# SimGEKI2_FrontIO.net
KiCad netlist of a schematic drawn in EasyEDA Pro
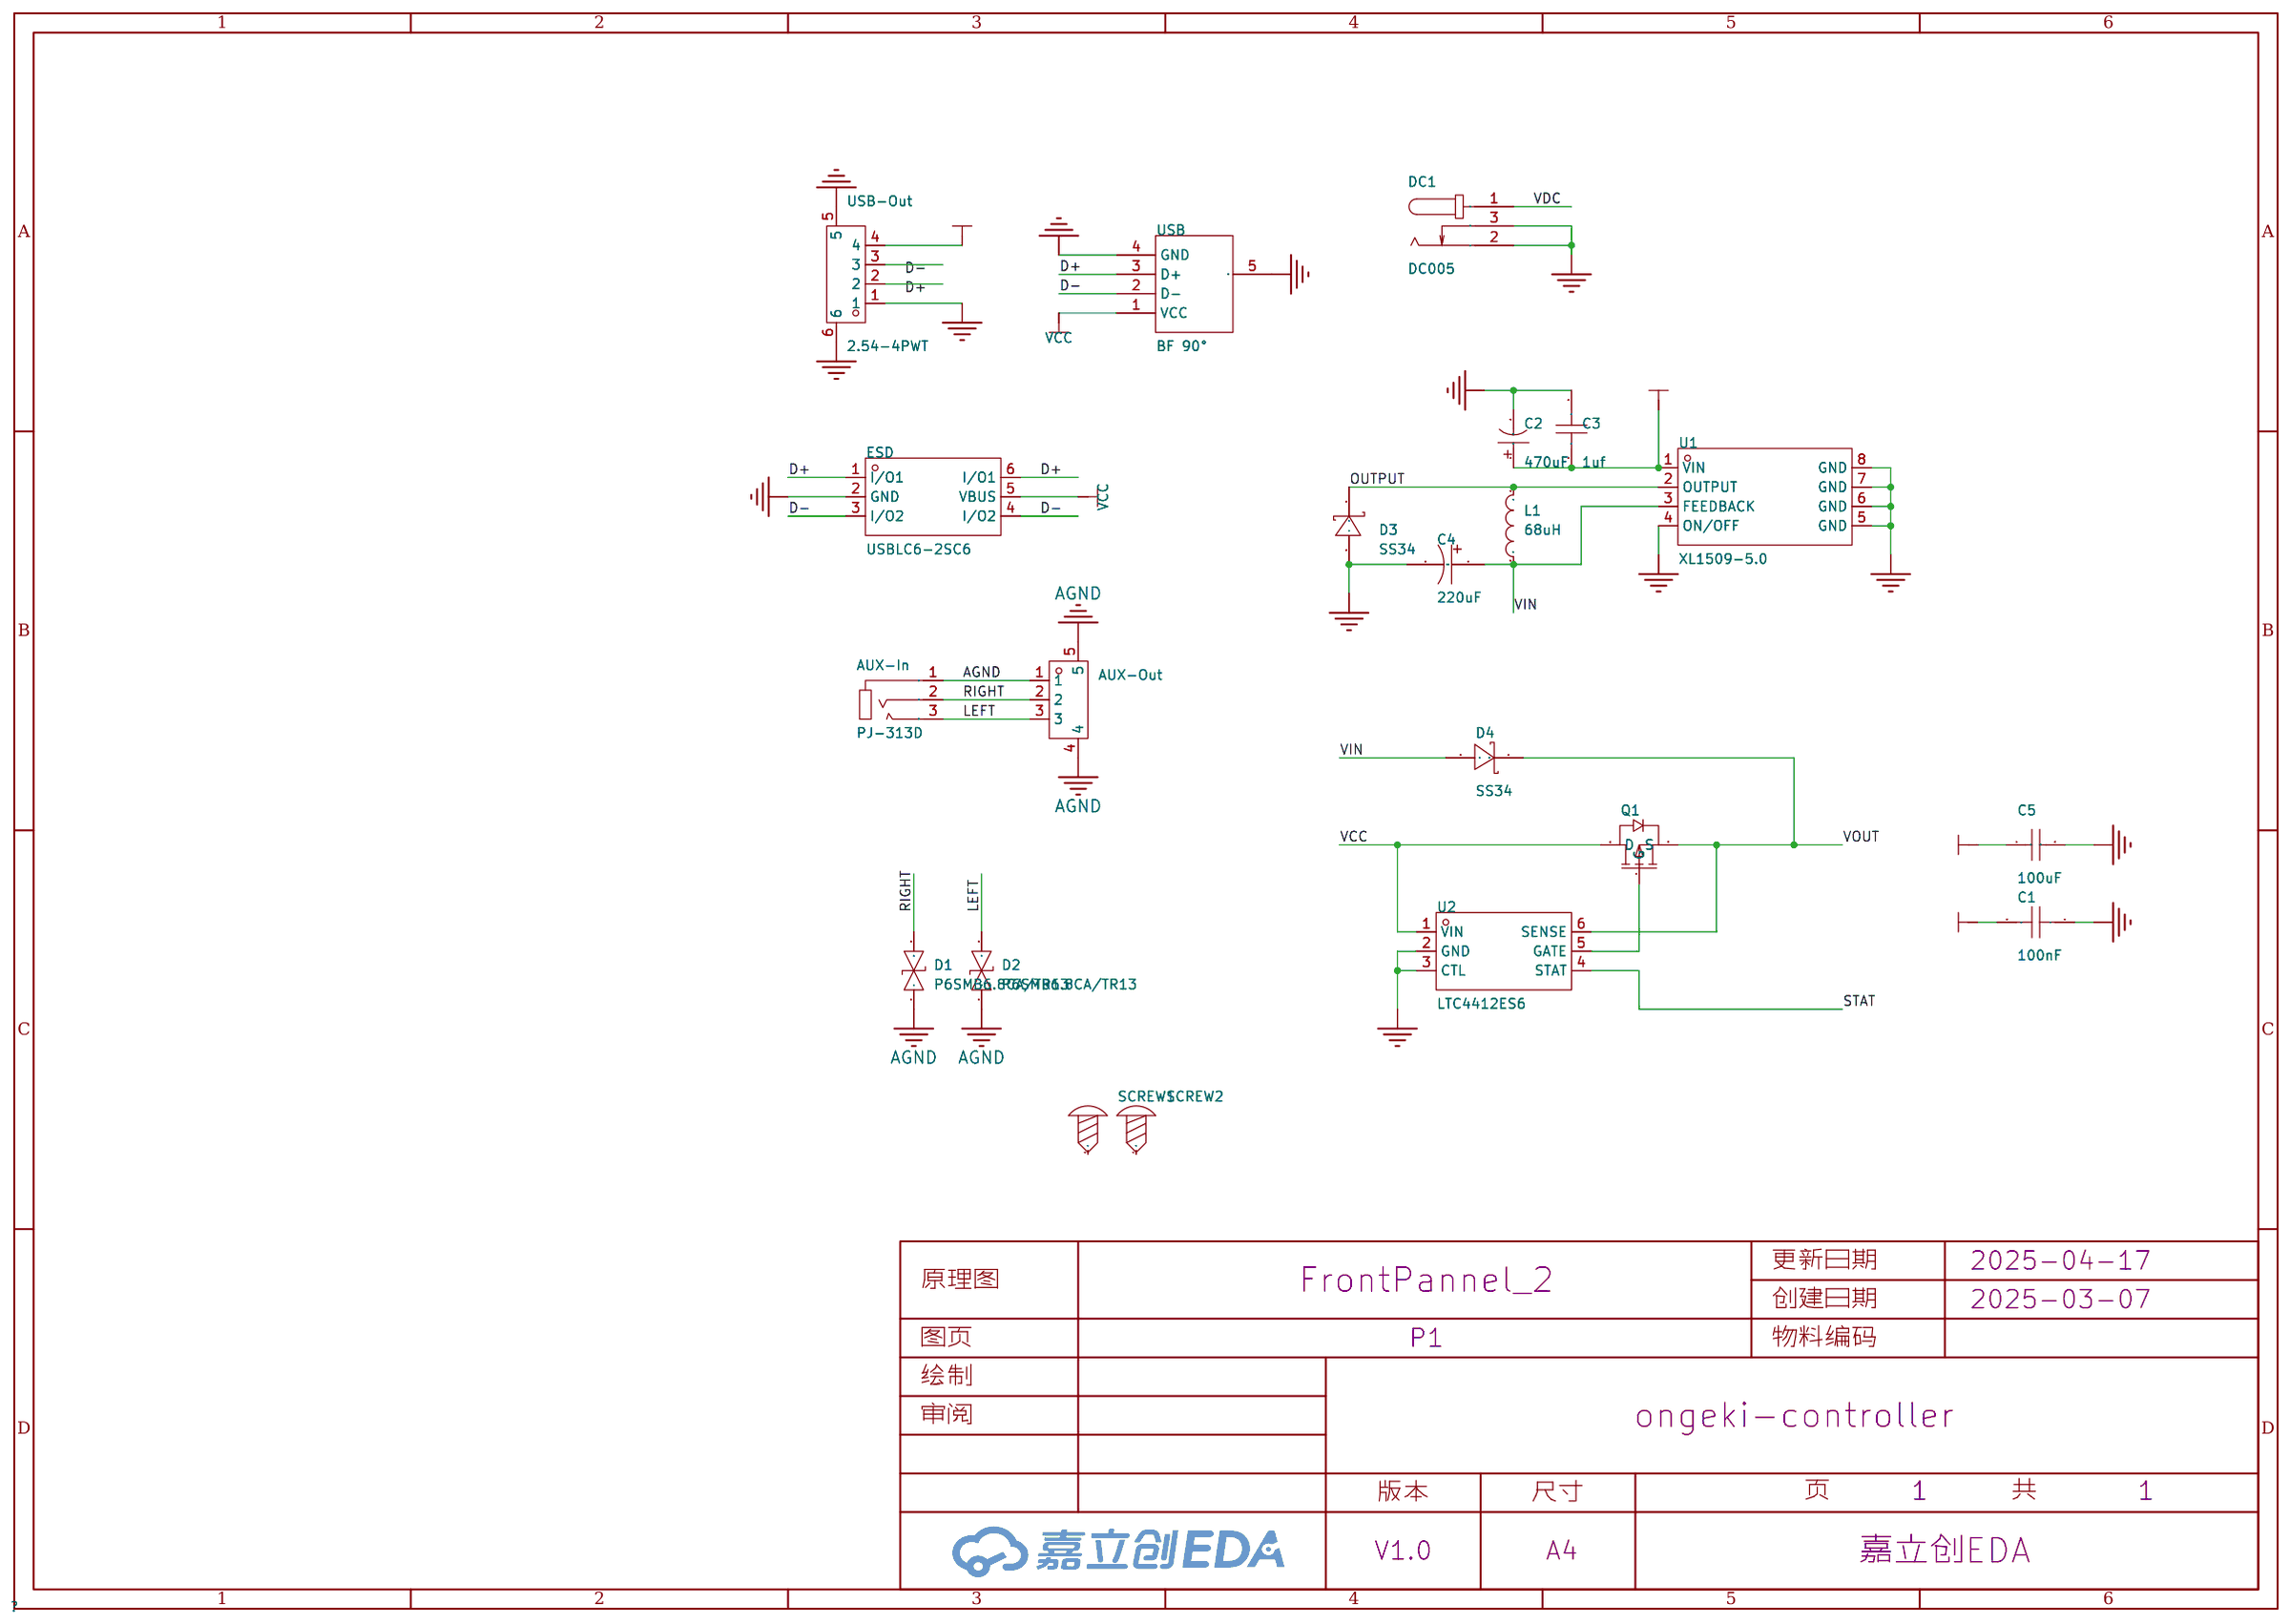
[diagram p0: schematic sheet]

(export (version "E")
  (design (tool "Eeschema 10.0.6"))
  (components
    (comp (ref "AUX-In")
      (value "PJ-313D")
      (footprint "easyedapro:AUDIO-SMD_PJ-313D-2")
      (description "连接器类型:3.5mm耳机座;额定电流:500mA;额定电压:30V;工作温度范围:-30°C~+70°C;")
      (fields (field (name "Manufacturer") "SHOU HAN(首韩)"))
      (libsource (lib "easyedapro") (part "PJ-313D_C668608"))
    )
    (comp (ref "AUX-Out")
      (value "WAFER-PH2.0-3PWB")
      (footprint "easyedapro:CONN-SMD_3P-P2.00_XUNPU_WAFER-PH2.0-3PWB")
      (description "插针结构:1x3P;间距:2mm;安装方式:卧贴;总PIN数:3P;排数:1;每排PIN数:3;额定电流:2A;工作温度范围:-25°C~+85°C;")
      (fields (field (name "Manufacturer") "XUNPU(讯普)"))
      (libsource (lib "easyedapro") (part "WAFER-PH2.0-3PWB"))
    )
    (comp (ref "C1")
      (value "100nF")
      (footprint "easyedapro:C0603")
      (libsource (lib "easyedapro") (part "CapAcitance"))
    )
    (comp (ref "C2")
      (value "470uF")
      (footprint "easyedapro:CAP-SMD_BD10.0-L10.3-W10.3-LS11.0-R-RD")
      (description "容值:470uF;精度:±20%;额定电压:35V;纹波电流:286mA@120Hz;等效串联电阻(ESR):-;")
      (fields (field (name "Manufacturer Part") "RVT1V471M1010") (field (name "Manufacturer") "ROQANG(容强)"))
      (libsource (lib "easyedapro") (part "RVT1V471M1010-C72519"))
    )
    (comp (ref "C3")
      (value "1uf")
      (footprint "easyedapro:C0603")
      (libsource (lib "easyedapro") (part "CapAcitance"))
    )
    (comp (ref "C4")
      (value "220uF")
      (fields (field (name "Manufacturer Part") "RVT1C221M0607") (field (name "Manufacturer") "ROQANG(容强)"))
      (libsource (lib "easyedapro") (part "VT1V221M0810"))
    )
    (comp (ref "C5")
      (value "100uF")
      (footprint "easyedapro:C1206")
      (description "容值:100uF;精度:±20%;额定电压:6.3V;材质(温度系数):X5R;")
      (fields
        (field (name "Manufacturer Part") "CL31A107MQHNNNE")
        (field (name "Manufacturer") "SAMSUNG(三星)")
      )
      (libsource (lib "easyedapro") (part "CL31A107MQHNNNE"))
    )
    (comp (ref "D1")
      (value "P6SMB6.8CA/TR13")
      (footprint "easyedapro:SMB_L4.6-W3.6-LS5.3-BI")
      (description "反向截止电压(Vrwm):5.8V;钳位电压:10.5V;峰值脉冲电流(Ipp):58.1A;峰值脉冲功率(Ppp):600W;击穿电压:6.45V;")
      (fields (field (name "Manufacturer") "Brightking(君耀电子)"))
      (libsource (lib "easyedapro") (part "P6SMB6.8CA-C78395"))
    )
    (comp (ref "D2")
      (value "P6SMB6.8CA/TR13")
      (footprint "easyedapro:SMB_L4.6-W3.6-LS5.3-BI")
      (description "反向截止电压(Vrwm):5.8V;钳位电压:10.5V;峰值脉冲电流(Ipp):58.1A;峰值脉冲功率(Ppp):600W;击穿电压:6.45V;")
      (fields (field (name "Manufacturer") "Brightking(君耀电子)"))
      (libsource (lib "easyedapro") (part "P6SMB6.8CA-C78395"))
    )
    (comp (ref "D3")
      (value "SS34")
      (footprint "easyedapro:SMA_L4.3-W2.6-LS5.2-RD")
      (description "二极管配置:独立式;正向压降(Vf):550mV@3A;直流反向耐压(Vr):40V;整流电流:3A;")
      (fields (field (name "Manufacturer") "MDD(辰达半导体)"))
      (libsource (lib "easyedapro") (part "SS34_C8678"))
    )
    (comp (ref "D4")
      (value "SS34")
      (footprint "easyedapro:SMA_L4.3-W2.6-LS5.2-RD")
      (description "二极管配置:独立式;正向压降(Vf):550mV@3A;直流反向耐压(Vr):40V;整流电流:3A;")
      (fields (field (name "Manufacturer") "MDD(辰达半导体)"))
      (libsource (lib "easyedapro") (part "SS34_C8678"))
    )
    (comp (ref "DC1")
      (value "DC005")
      (footprint "easyedapro:DC-IN-TH_DC005")
      (description "连接器类型:DC电源插座;安装方式:弯插;触点内径:2mm;触点外径:6.3mm;额定电流:500mA;额定电压:30V;工作温度范围:-25°C~+70°C;")
      (fields (field (name "Manufacturer") "SHOU HAN(首韩)"))
      (libsource (lib "easyedapro") (part "DC005_C431533"))
    )
    (comp (ref "ESD")
      (value "USBLC6-2SC6")
      (footprint "easyedapro:SOT-23-6_L2.9-W1.6-P0.95-LS2.8-BL")
      (fields (field (name "Manufacturer") "UMW(广东友台半导体)"))
      (libsource (lib "easyedapro") (part "USBLC6-2SC6_C2687116"))
    )
    (comp (ref "L1")
      (value "68uH")
      (footprint "easyedapro:IND-SMD_L7.1-W6.6")
      (description "电感值:68uH;精度:±20%;额定电流:1.5A;饱和电流(Isat):2A;类型:一体成型电感;")
      (fields (field (name "Manufacturer Part") "SMMS0650-680M") (field (name "Manufacturer") "SXN(顺翔诺)"))
      (libsource (lib "easyedapro") (part "SMMS0650-680M"))
    )
    (comp (ref "Q1")
      (value "~")
      (footprint "easyedapro:AO3401A_SOT-23-3")
      (libsource (lib "easyedapro") (part "P_MOS"))
    )
    (comp (ref "SCREW1")
      (value "~")
      (footprint "easyedapro:M4螺丝")
      (libsource (lib "easyedapro") (part "螺丝孔"))
    )
    (comp (ref "SCREW2")
      (value "~")
      (footprint "easyedapro:M4螺丝")
      (libsource (lib "easyedapro") (part "螺丝孔"))
    )
    (comp (ref "U1")
      (value "XL1509-5.0")
      (footprint "easyedapro:SOIC-8_L4.9-W3.9-P1.27-LS6.0-TR")
      (description "功能类型:降压型;输出类型:固定;工作电压:4.5V~40V;输出电压:5V;输出电流:2A;")
      (fields (field (name "Manufacturer") "UMW(友台半导体)"))
      (libsource (lib "easyedapro") (part "XL1509-5.0_C2902368"))
    )
    (comp (ref "U2")
      (value "LTC4412ES6")
      (footprint "easyedapro:TSOT-23-6_L2.9-W1.6-P0.95-LS2.8-BR")
      (description "电源电压:2.5V~28V;")
      (fields (field (name "Manufacturer") "ADI(亚德诺)"))
      (libsource (lib "easyedapro") (part "LTC4412ES6#TRPBF"))
    )
    (comp (ref "USB")
      (value "BF 90°")
      (footprint "easyedapro:USB-B_TH_BF90")
      (description "连接器类型:Type-B;标准:USB 2.0;公母:母;端口数量:1;触点数量:4P;安装方式:弯插;额定电流 - 电源:1.5A;工作温度范围:-25°C~+85°C;")
      (fields (field (name "Manufacturer") "SHOU HAN(首韩)"))
      (libsource (lib "easyedapro") (part "BF 90°"))
    )
    (comp (ref "USB-Out")
      (value "2.54-4PWT")
      (footprint "easyedapro:COMM-SMD_4P-P2.50_SHOUHAN_2.54-4PWT")
      (description "插针结构:1x4P;间距:2.5mm;公母:公;安装方式:卧贴;排数:1;每排PIN数:4;额定电流:3A;工作温度范围:-25°C~+85°C;")
      (fields (field (name "Manufacturer") "SHOU HAN(首韩)"))
      (libsource (lib "easyedapro") (part "2.54-4PWT"))
    )
  )
  (nets
    (net (code "1") (name "/D+") (class "Default")
      (node (ref "ESD") (pin "1") (pinfunction "I/O1_1") (pintype "unspecified"))
      (node (ref "ESD") (pin "6") (pinfunction "I/O1_6") (pintype "unspecified"))
      (node (ref "USB") (pin "3") (pinfunction "D+_3") (pintype "input"))
      (node (ref "USB-Out") (pin "2") (pinfunction "2_2") (pintype "unspecified"))
    )
    (net (code "2") (name "/D-") (class "Default")
      (node (ref "ESD") (pin "3") (pinfunction "I/O2_3") (pintype "unspecified"))
      (node (ref "ESD") (pin "4") (pinfunction "I/O2_4") (pintype "unspecified"))
      (node (ref "USB") (pin "2") (pinfunction "D-_2") (pintype "input"))
      (node (ref "USB-Out") (pin "3") (pinfunction "3_3") (pintype "unspecified"))
    )
    (net (code "3") (name "/LEFT") (class "Default")
      (node (ref "AUX-In") (pin "3") (pinfunction "3_3") (pintype "unspecified"))
      (node (ref "AUX-Out") (pin "3") (pinfunction "3_3") (pintype "unspecified"))
      (node (ref "D2") (pin "2") (pinfunction "2_2") (pintype "unspecified"))
    )
    (net (code "4") (name "/OUTPUT") (class "Default")
      (node (ref "D3") (pin "1") (pinfunction "K_1") (pintype "unspecified"))
      (node (ref "L1") (pin "1") (pinfunction "1_1") (pintype "unspecified"))
      (node (ref "U1") (pin "2") (pinfunction "OUTPUT_2") (pintype "unspecified"))
    )
    (net (code "5") (name "/RIGHT") (class "Default")
      (node (ref "AUX-In") (pin "2") (pinfunction "2_2") (pintype "unspecified"))
      (node (ref "AUX-Out") (pin "2") (pinfunction "2_2") (pintype "unspecified"))
      (node (ref "D1") (pin "2") (pinfunction "2_2") (pintype "unspecified"))
    )
    (net (code "6") (name "/STAT") (class "Default")
      (node (ref "U2") (pin "4") (pinfunction "STAT_4") (pintype "unspecified"))
    )
    (net (code "7") (name "/VIN") (class "Default")
      (node (ref "C4") (pin "1") (pinfunction "1_1") (pintype "unspecified"))
      (node (ref "D4") (pin "2") (pinfunction "A_2") (pintype "unspecified"))
      (node (ref "L1") (pin "2") (pinfunction "2_2") (pintype "unspecified"))
      (node (ref "U1") (pin "3") (pinfunction "FEEDBACK_3") (pintype "unspecified"))
    )
    (net (code "8") (name "AGND") (class "Default")
      (node (ref "AUX-In") (pin "1") (pinfunction "1_1") (pintype "unspecified"))
      (node (ref "AUX-Out") (pin "1") (pinfunction "1_1") (pintype "unspecified"))
      (node (ref "AUX-Out") (pin "4") (pinfunction "4_4") (pintype "unspecified"))
      (node (ref "AUX-Out") (pin "5") (pinfunction "5_5") (pintype "unspecified"))
      (node (ref "D1") (pin "1") (pinfunction "1_1") (pintype "unspecified"))
      (node (ref "D2") (pin "1") (pinfunction "1_1") (pintype "unspecified"))
    )
    (net (code "9") (name "GND") (class "Default")
      (node (ref "C1") (pin "1") (pinfunction "1_1") (pintype "input"))
      (node (ref "C2") (pin "2") (pinfunction "2_2") (pintype "input"))
      (node (ref "C3") (pin "2") (pinfunction "2_2") (pintype "input"))
      (node (ref "C4") (pin "2") (pinfunction "2_2") (pintype "unspecified"))
      (node (ref "C5") (pin "2") (pinfunction "2_2") (pintype "input"))
      (node (ref "D3") (pin "2") (pinfunction "A_2") (pintype "unspecified"))
      (node (ref "DC1") (pin "2") (pinfunction "2_2") (pintype "unspecified"))
      (node (ref "DC1") (pin "3") (pinfunction "3_3") (pintype "unspecified"))
      (node (ref "ESD") (pin "2") (pinfunction "GND_2") (pintype "unspecified"))
      (node (ref "U1") (pin "4") (pinfunction "ON/OFF_4") (pintype "unspecified"))
      (node (ref "U1") (pin "5") (pinfunction "GND_5") (pintype "unspecified"))
      (node (ref "U1") (pin "6") (pinfunction "GND_6") (pintype "unspecified"))
      (node (ref "U1") (pin "7") (pinfunction "GND_7") (pintype "unspecified"))
      (node (ref "U1") (pin "8") (pinfunction "GND_8") (pintype "unspecified"))
      (node (ref "U2") (pin "2") (pinfunction "GND_2") (pintype "unspecified"))
      (node (ref "U2") (pin "3") (pinfunction "CTL_3") (pintype "unspecified"))
      (node (ref "USB") (pin "4") (pinfunction "GND_4") (pintype "input"))
      (node (ref "USB") (pin "5") (pinfunction "EH_5") (pintype "unspecified"))
      (node (ref "USB-Out") (pin "1") (pinfunction "1_1") (pintype "unspecified"))
      (node (ref "USB-Out") (pin "5") (pinfunction "5_5") (pintype "unspecified"))
      (node (ref "USB-Out") (pin "6") (pinfunction "6_6") (pintype "unspecified"))
    )
    (net (code "10") (name "Net-(Q1-G)") (class "Default")
      (node (ref "Q1") (pin "1") (pinfunction "G_1") (pintype "input"))
      (node (ref "U2") (pin "5") (pinfunction "GATE_5") (pintype "unspecified"))
    )
    (net (code "11") (name "VCC") (class "Default")
      (node (ref "ESD") (pin "5") (pinfunction "VBUS_5") (pintype "unspecified"))
      (node (ref "Q1") (pin "3") (pinfunction "D_3") (pintype "input"))
      (node (ref "U2") (pin "1") (pinfunction "VIN_1") (pintype "unspecified"))
      (node (ref "USB") (pin "1") (pinfunction "VCC_1") (pintype "input"))
    )
    (net (code "12") (name "VDC") (class "Default")
      (node (ref "C2") (pin "1") (pinfunction "1_1") (pintype "input"))
      (node (ref "C3") (pin "1") (pinfunction "1_1") (pintype "input"))
      (node (ref "DC1") (pin "1") (pinfunction "1_1") (pintype "unspecified"))
      (node (ref "U1") (pin "1") (pinfunction "VIN_1") (pintype "unspecified"))
    )
    (net (code "13") (name "VOUT") (class "Default")
      (node (ref "C1") (pin "2") (pinfunction "2_2") (pintype "input"))
      (node (ref "C5") (pin "1") (pinfunction "1_1") (pintype "input"))
      (node (ref "D4") (pin "1") (pinfunction "K_1") (pintype "unspecified"))
      (node (ref "Q1") (pin "2") (pinfunction "S_2") (pintype "input"))
      (node (ref "U2") (pin "6") (pinfunction "SENSE_6") (pintype "unspecified"))
      (node (ref "USB-Out") (pin "4") (pinfunction "4_4") (pintype "unspecified"))
    )
    (net (code "14") (name "unconnected-(SCREW1-Pad1)") (class "Default")
      (node (ref "SCREW1") (pin "1") (pinfunction "1_1") (pintype "input"))
    )
    (net (code "15") (name "unconnected-(SCREW2-Pad1)") (class "Default")
      (node (ref "SCREW2") (pin "1") (pinfunction "1_1") (pintype "input"))
    )
  )
)
